# bat_pak_reva.net
KiCad netlist of a schematic drawn in Altium Designer
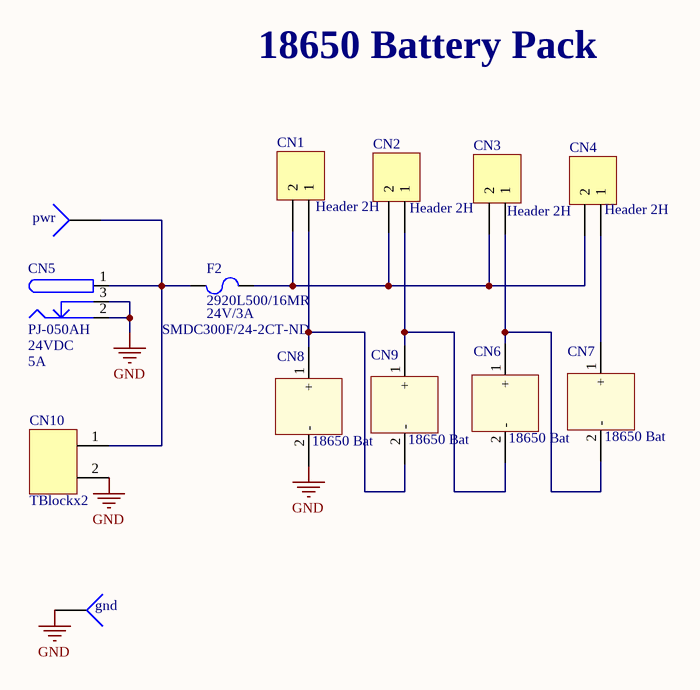
[diagram p0: bat_pak_reva.SchDoc]

(export (version "E")
  (design (tool "Eeschema 10.0.6"))
  (components
    (comp (ref "CN1")
      (value "Header 2H")
      (footprint "HDR1X2H")
      (description "Header, 2-Pin, Right Angle")
      (fields
        (field (name "MANUFACTURER PART NUMBER") "M20-9960245")
        (field (name "MANUFACTURER") "Harwin Inc.")
        (field (name "PUBLISHER") "Altium Limited")
      )
      (libsource (lib "OLogic Nexus Vault") (part "Header 2H"))
    )
    (comp (ref "CN2")
      (value "Header 2H")
      (footprint "HDR1X2H")
      (description "Header, 2-Pin, Right Angle")
      (fields
        (field (name "MANUFACTURER PART NUMBER") "M20-9960245")
        (field (name "MANUFACTURER") "Harwin Inc.")
        (field (name "PUBLISHER") "Altium Limited")
      )
      (libsource (lib "OLogic Nexus Vault") (part "Header 2H"))
    )
    (comp (ref "CN3")
      (value "Header 2H")
      (footprint "HDR1X2H")
      (description "Header, 2-Pin, Right Angle")
      (fields
        (field (name "MANUFACTURER PART NUMBER") "M20-9960245")
        (field (name "MANUFACTURER") "Harwin Inc.")
        (field (name "PUBLISHER") "Altium Limited")
      )
      (libsource (lib "OLogic Nexus Vault") (part "Header 2H"))
    )
    (comp (ref "CN4")
      (value "Header 2H")
      (footprint "HDR1X2H")
      (description "Header, 2-Pin, Right Angle")
      (fields
        (field (name "MANUFACTURER PART NUMBER") "M20-9960245")
        (field (name "MANUFACTURER") "Harwin Inc.")
        (field (name "PUBLISHER") "Altium Limited")
      )
      (libsource (lib "OLogic Nexus Vault") (part "Header 2H"))
    )
    (comp (ref "CN5")
      (value "PJ-050AH")
      (footprint "PJ-050AH")
      (description "Power Barrel Connector Jack 2.00mm ID 5.50mm OD Through Hole, Right Angle")
      (fields
        (field (name "VOLTAGE - RATED") "24VDC")
        (field (name "CURRENT RATING") "5A")
        (field (name "MANUFACTURER") "CUI")
      )
      (libsource (lib "OLogic Nexus Vault") (part "PJ-050AH"))
    )
    (comp (ref "CN6")
      (value "18650 Bat")
      (footprint "battery_holder_18650")
      (libsource (lib "*") (part "battery_holder_18650"))
    )
    (comp (ref "CN7")
      (value "18650 Bat")
      (footprint "battery_holder_18650")
      (libsource (lib "*") (part "battery_holder_18650"))
    )
    (comp (ref "CN8")
      (value "18650 Bat")
      (footprint "battery_holder_18650")
      (libsource (lib "*") (part "battery_holder_18650"))
    )
    (comp (ref "CN9")
      (value "18650 Bat")
      (footprint "battery_holder_18650")
      (libsource (lib "*") (part "battery_holder_18650"))
    )
    (comp (ref "CN10")
      (value "TBlockx2")
      (footprint "TB-5MM-X2")
      (description "5mm Terminal Block x 2")
      (fields (field (name "MANUFACTURER") "OST") (field (name "MPN") "OSTTC020160"))
      (libsource (lib "OLogic Nexus Vault") (part "TBlockx2"))
    )
    (comp (ref "F2")
      (value "2920L500/16MR")
      (footprint "2920 Fuse")
      (description "PTC RESET FUSE 16V 5A 2920")
      (libsource (lib "OLogic Nexus Vault") (part "FUSE_GENERIC"))
    )
    (comp (ref "gnd")
      (value "~")
      (footprint "TestPoint-TH 35 mil")
      (description "Test Point")
      (libsource (lib "OLogic-Misc") (part "TestPoint"))
    )
    (comp (ref "pwr")
      (value "~")
      (footprint "TestPoint-TH 35 mil")
      (description "Test Point")
      (libsource (lib "OLogic-Misc") (part "TestPoint"))
    )
  )
  (nets
    (net (code "1") (name "GND") (class "Default")
      (node (ref "CN10") (pin "2") (pinfunction "2_2") (pintype "passive"))
      (node (ref "CN5") (pin "2") (pinfunction "2_2") (pintype "power_in"))
      (node (ref "CN5") (pin "3") (pinfunction "3_3") (pintype "power_in"))
      (node (ref "CN8") (pin "2") (pinfunction "-_2") (pintype "passive"))
      (node (ref "gnd") (pin "1") (pinfunction "1_1") (pintype "passive"))
    )
    (net (code "2") (name "Net-(CN1-Pad2)") (class "Default")
      (node (ref "CN1") (pin "2") (pinfunction "2_2") (pintype "passive"))
      (node (ref "CN2") (pin "2") (pinfunction "2_2") (pintype "passive"))
      (node (ref "CN3") (pin "2") (pinfunction "2_2") (pintype "passive"))
      (node (ref "CN4") (pin "2") (pinfunction "2_2") (pintype "passive"))
      (node (ref "F2") (pin "2") (pinfunction "2_2") (pintype "power_in"))
    )
    (net (code "3") (name "Net-(CN6-+)") (class "Default")
      (node (ref "CN3") (pin "1") (pinfunction "1_1") (pintype "passive"))
      (node (ref "CN6") (pin "1") (pinfunction "+_1") (pintype "passive"))
      (node (ref "CN7") (pin "2") (pinfunction "-_2") (pintype "passive"))
    )
    (net (code "4") (name "Net-(CN6--)") (class "Default")
      (node (ref "CN2") (pin "1") (pinfunction "1_1") (pintype "passive"))
      (node (ref "CN6") (pin "2") (pinfunction "-_2") (pintype "passive"))
      (node (ref "CN9") (pin "1") (pinfunction "+_1") (pintype "passive"))
    )
    (net (code "5") (name "Net-(CN7-+)") (class "Default")
      (node (ref "CN4") (pin "1") (pinfunction "1_1") (pintype "passive"))
      (node (ref "CN7") (pin "1") (pinfunction "+_1") (pintype "passive"))
    )
    (net (code "6") (name "Net-(CN8-+)") (class "Default")
      (node (ref "CN1") (pin "1") (pinfunction "1_1") (pintype "passive"))
      (node (ref "CN8") (pin "1") (pinfunction "+_1") (pintype "passive"))
      (node (ref "CN9") (pin "2") (pinfunction "-_2") (pintype "passive"))
    )
    (net (code "7") (name "Net-(CN10-Pad1)") (class "Default")
      (node (ref "CN10") (pin "1") (pinfunction "1_1") (pintype "passive"))
      (node (ref "CN5") (pin "1") (pinfunction "1_1") (pintype "power_in"))
      (node (ref "F2") (pin "1") (pinfunction "1_1") (pintype "power_in"))
      (node (ref "pwr") (pin "1") (pinfunction "1_1") (pintype "passive"))
    )
  )
)
